# isoSPI_to_SPI.net
KiCad netlist of a schematic drawn in Altium Designer
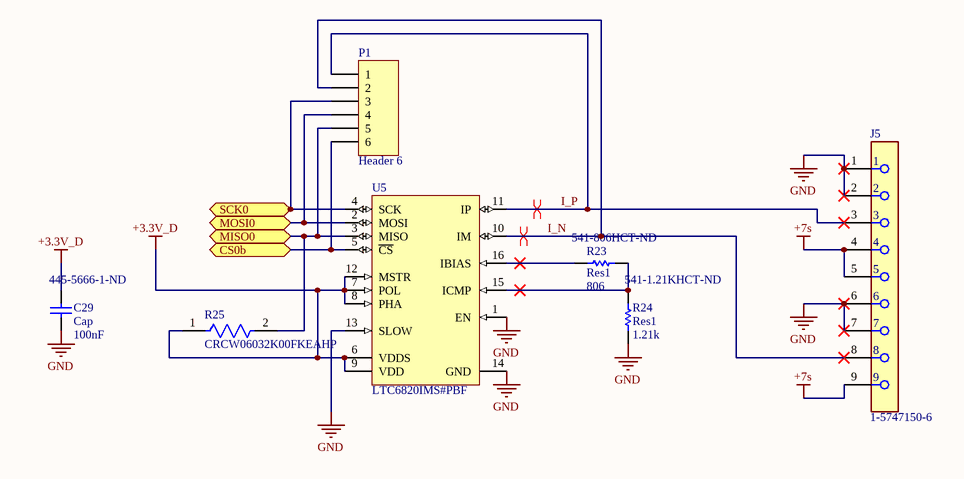
[diagram p0: isoSPI_to_SPI.SchDoc]

(export (version "E")
  (design (tool "Eeschema 10.0.6"))
  (components
    (comp (ref "C29")
      (value "Cap")
      (footprint "J1-0603")
      (description "TDK - CGA3E2X7R1H104K080AA. - CERAMIC CAPACITOR, 0.1UF, 50V, X7R, 0603, FULL REEL")
      (fields
        (field (name "ALTIUM_VALUE") "100nF")
        (field (name "SUPPLIER PART NUMBER 1") "445-5666-1-ND")
        (field (name "MANUFACTURER") "TDK")
        (field (name "MANUFACTURER PART NUMBER") "CGA3E2X7R1H104K080AA")
        (field (name "PUBLISHER") "Altium Limited")
      )
      (libsource (lib "Miscellaneous Devices") (part "Cap"))
    )
    (comp (ref "J5")
      (value "1-5747150-6")
      (footprint "FP-1-5747150-6-MFG")
      (description "CONN D-SUB RCPT 9POS VERT SOLDER")
      (fields
        (field (name "OCTOPART") "https://octopart.com/1-5747150-6-te+connectivity-39500344")
        (field (name "MANUFACTURER") "TE Connectivity")
      )
      (libsource (lib "Altium Content Vault") (part "deee9d0d87fff07c08bdfa5b86cd5a5"))
    )
    (comp (ref "P1")
      (value "Header 6")
      (footprint "HDR1X6")
      (description "Header, 6-Pin")
      (fields (field (name "PUBLISHER") "Altium Limited"))
      (libsource (lib "Miscellaneous Connectors") (part "Header 6"))
    )
    (comp (ref "R23")
      (value "Res1")
      (footprint "J1-0603")
      (description "RES SMD 806 OHM 1% 1/10W 0603")
      (fields
        (field (name "ALTIUM_VALUE") "806")
        (field (name "SUPPLIER PART NUMBER 1") "541-806HCT-ND")
        (field (name "MANUFACTURER") "Vishay")
        (field (name "MANUFACTURER PART NUMBER") "CRCW0603806RFKEA")
        (field (name "PUBLISHER") "Altium Limited")
      )
      (libsource (lib "Miscellaneous Devices") (part "Res1"))
    )
    (comp (ref "R24")
      (value "Res1")
      (footprint "J1-0603")
      (description "Res Thick Film 0603 1.21K Ohm 1% 1/10W 100ppm/C Molded SMD Paper T/R")
      (fields
        (field (name "ALTIUM_VALUE") "1.21k")
        (field (name "SUPPLIER PART NUMBER 1") "541-1.21KHCT-ND")
        (field (name "MANUFACTURER") "Vishay")
        (field (name "MANUFACTURER PART NUMBER") "CRCW06031K21FKEA")
        (field (name "PUBLISHER") "Altium Limited")
      )
      (libsource (lib "Miscellaneous Devices") (part "Res1"))
    )
    (comp (ref "R25")
      (value "CRCW06032K00FKEAHP")
      (footprint "FP-CRCW0603-HPe3-IPC_C")
      (description "RES Thick Film, 2kΩ, 1%, 0.33W, 100ppm/°C, 0603")
      (fields (field (name "TOLERANCE") "1%"))
      (libsource (lib "Altium Content Vault") (part "1029c3af85768c4190bb7ad29bc67b5"))
    )
    (comp (ref "U5")
      (value "LTC6820IMS#PBF")
      (footprint "LT-MS-16_M")
      (description "IsoSPI Isolated Communication Interface, 2.7 to 5.5 V, -40 to 85 degC, 16-Pin MSOP (MS), Pb-Free")
      (fields (field (name "MANUFACTURER") "Linear Technology"))
      (libsource (lib "Altium Content Vault") (part "LT-LTC6820-MS-16"))
    )
  )
  (nets
    (net (code "1") (name "+3.3V_D") (class "Default")
      (node (ref "C29") (pin "2") (pinfunction "2_2") (pintype "passive"))
      (node (ref "R25") (pin "1") (pinfunction "1_1") (pintype "passive"))
      (node (ref "U5") (pin "12") (pinfunction "MSTR_12") (pintype "input"))
      (node (ref "U5") (pin "6") (pinfunction "VDDS_6") (pintype "power_in"))
      (node (ref "U5") (pin "7") (pinfunction "POL_7") (pintype "input"))
      (node (ref "U5") (pin "8") (pinfunction "PHA_8") (pintype "input"))
      (node (ref "U5") (pin "9") (pinfunction "VDD_9") (pintype "power_in"))
    )
    (net (code "2") (name "+7s") (class "Default")
      (node (ref "J5") (pin "4") (pinfunction "4_4") (pintype "passive"))
      (node (ref "J5") (pin "5") (pinfunction "5_5") (pintype "passive"))
      (node (ref "J5") (pin "9") (pinfunction "9_9") (pintype "passive"))
    )
    (net (code "3") (name "/CS0b") (class "Default")
      (node (ref "P1") (pin "6") (pinfunction "6_6") (pintype "passive"))
      (node (ref "U5") (pin "5") (pinfunction "~{CS}_5") (pintype "bidirectional"))
    )
    (net (code "4") (name "/I_N") (class "Default")
      (node (ref "J5") (pin "8") (pinfunction "8_8") (pintype "passive"))
      (node (ref "P1") (pin "2") (pinfunction "2_2") (pintype "passive"))
      (node (ref "U5") (pin "10") (pinfunction "IM_10") (pintype "bidirectional"))
    )
    (net (code "5") (name "/I_P") (class "Default")
      (node (ref "J5") (pin "3") (pinfunction "3_3") (pintype "passive"))
      (node (ref "P1") (pin "1") (pinfunction "1_1") (pintype "passive"))
      (node (ref "U5") (pin "11") (pinfunction "IP_11") (pintype "bidirectional"))
    )
    (net (code "6") (name "/MISO0") (class "Default")
      (node (ref "P1") (pin "5") (pinfunction "5_5") (pintype "passive"))
      (node (ref "R25") (pin "2") (pinfunction "2_2") (pintype "passive"))
      (node (ref "U5") (pin "3") (pinfunction "MISO_3") (pintype "bidirectional"))
    )
    (net (code "7") (name "/MOSI0") (class "Default")
      (node (ref "P1") (pin "4") (pinfunction "4_4") (pintype "passive"))
      (node (ref "U5") (pin "2") (pinfunction "MOSI_2") (pintype "bidirectional"))
    )
    (net (code "8") (name "/SCK0") (class "Default")
      (node (ref "P1") (pin "3") (pinfunction "3_3") (pintype "passive"))
      (node (ref "U5") (pin "4") (pinfunction "SCK_4") (pintype "bidirectional"))
    )
    (net (code "9") (name "GND") (class "Default")
      (node (ref "C29") (pin "1") (pinfunction "1_1") (pintype "passive"))
      (node (ref "J5") (pin "1") (pinfunction "1_1") (pintype "passive"))
      (node (ref "J5") (pin "2") (pinfunction "2_2") (pintype "passive"))
      (node (ref "J5") (pin "6") (pinfunction "6_6") (pintype "passive"))
      (node (ref "J5") (pin "7") (pinfunction "7_7") (pintype "passive"))
      (node (ref "R24") (pin "1") (pinfunction "1_1") (pintype "passive"))
      (node (ref "U5") (pin "1") (pinfunction "EN_1") (pintype "input"))
      (node (ref "U5") (pin "13") (pinfunction "SLOW_13") (pintype "input"))
      (node (ref "U5") (pin "14") (pinfunction "GND_14") (pintype "power_in"))
    )
    (net (code "10") (name "Net-(U5-IBIAS)") (class "Default")
      (node (ref "R23") (pin "1") (pinfunction "1_1") (pintype "passive"))
      (node (ref "U5") (pin "16") (pinfunction "IBIAS_16") (pintype "input"))
    )
    (net (code "11") (name "Net-(U5-ICMP)") (class "Default")
      (node (ref "R23") (pin "2") (pinfunction "2_2") (pintype "passive"))
      (node (ref "R24") (pin "2") (pinfunction "2_2") (pintype "passive"))
      (node (ref "U5") (pin "15") (pinfunction "ICMP_15") (pintype "input"))
    )
  )
)
